# IMU.net
KiCad netlist of a schematic drawn in Altium Designer
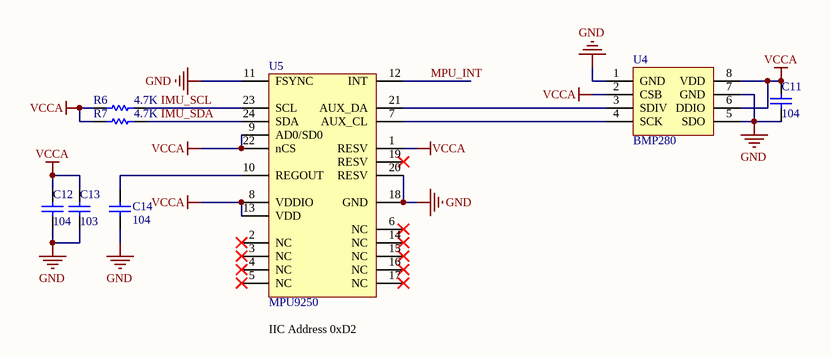
[diagram p0: IMU.SchDoc]

(export (version "E")
  (design (tool "Eeschema 10.0.6"))
  (components
    (comp (ref "C11")
      (value "104")
      (footprint "C0603")
      (description "电容")
      (fields (field (name "PUBLISHER") "Altium Limited"))
      (libsource (lib "Devices") (part "C0603"))
    )
    (comp (ref "C12")
      (value "104")
      (footprint "C0603")
      (description "电容")
      (fields (field (name "PUBLISHER") "Altium Limited"))
      (libsource (lib "Devices") (part "C0603"))
    )
    (comp (ref "C13")
      (value "103")
      (footprint "C0603")
      (description "电容")
      (fields (field (name "PUBLISHER") "Altium Limited"))
      (libsource (lib "Devices") (part "C0603"))
    )
    (comp (ref "C14")
      (value "104")
      (footprint "C0603")
      (description "电容")
      (fields (field (name "PUBLISHER") "Altium Limited"))
      (libsource (lib "Devices") (part "C0603"))
    )
    (comp (ref "R6")
      (value "4.7K")
      (footprint "R0603")
      (description "电阻")
      (fields (field (name "PUBLISHER") "Altium Limited"))
      (libsource (lib "Devices") (part "RES0603"))
    )
    (comp (ref "R7")
      (value "4.7K")
      (footprint "R0603")
      (description "电阻")
      (fields (field (name "PUBLISHER") "Altium Limited"))
      (libsource (lib "Devices") (part "RES0603"))
    )
    (comp (ref "U4")
      (value "BMP280")
      (footprint "LGA-8")
      (description "气压剂")
      (libsource (lib "IC") (part "BMP280"))
    )
    (comp (ref "U5")
      (value "MPU9250")
      (footprint "QFN-24-0.4")
      (description "9轴运动处理传感器")
      (libsource (lib "IC") (part "MPU9250"))
    )
  )
  (nets
    (net (code "1") (name "/IMU_SCL") (class "Default")
      (node (ref "R6") (pin "2") (pinfunction "2_2") (pintype "passive"))
      (node (ref "U5") (pin "23") (pinfunction "SCL_23") (pintype "passive"))
    )
    (net (code "2") (name "/IMU_SDA") (class "Default")
      (node (ref "R7") (pin "2") (pinfunction "2_2") (pintype "passive"))
      (node (ref "U5") (pin "24") (pinfunction "SDA_24") (pintype "passive"))
    )
    (net (code "3") (name "/MPU_INT") (class "Default")
      (node (ref "U5") (pin "12") (pinfunction "INT_12") (pintype "passive"))
    )
    (net (code "4") (name "GND") (class "Default")
      (node (ref "C11") (pin "1") (pinfunction "1_1") (pintype "passive"))
      (node (ref "C12") (pin "1") (pinfunction "1_1") (pintype "passive"))
      (node (ref "C13") (pin "1") (pinfunction "1_1") (pintype "passive"))
      (node (ref "C14") (pin "1") (pinfunction "1_1") (pintype "passive"))
      (node (ref "U4") (pin "1") (pinfunction "GND_1") (pintype "passive"))
      (node (ref "U4") (pin "5") (pinfunction "SDO_5") (pintype "passive"))
      (node (ref "U4") (pin "7") (pinfunction "GND_7") (pintype "passive"))
      (node (ref "U5") (pin "11") (pinfunction "FSYNC_11") (pintype "passive"))
      (node (ref "U5") (pin "18") (pinfunction "GND_18") (pintype "passive"))
      (node (ref "U5") (pin "20") (pinfunction "RESV_20") (pintype "passive"))
    )
    (net (code "5") (name "Net-(U4-SCK)") (class "Default")
      (node (ref "U4") (pin "4") (pinfunction "SCK_4") (pintype "passive"))
      (node (ref "U5") (pin "7") (pinfunction "AUX_CL_7") (pintype "passive"))
    )
    (net (code "6") (name "Net-(U4-SDIV)") (class "Default")
      (node (ref "U4") (pin "3") (pinfunction "SDIV_3") (pintype "passive"))
      (node (ref "U5") (pin "21") (pinfunction "AUX_DA_21") (pintype "passive"))
    )
    (net (code "7") (name "Net-(U5-REGOUT)") (class "Default")
      (node (ref "C14") (pin "2") (pinfunction "2_2") (pintype "passive"))
      (node (ref "U5") (pin "10") (pinfunction "REGOUT_10") (pintype "passive"))
    )
    (net (code "8") (name "VCCA") (class "Default")
      (node (ref "C11") (pin "2") (pinfunction "2_2") (pintype "passive"))
      (node (ref "C12") (pin "2") (pinfunction "2_2") (pintype "passive"))
      (node (ref "C13") (pin "2") (pinfunction "2_2") (pintype "passive"))
      (node (ref "R6") (pin "1") (pinfunction "1_1") (pintype "passive"))
      (node (ref "R7") (pin "1") (pinfunction "1_1") (pintype "passive"))
      (node (ref "U4") (pin "2") (pinfunction "CSB_2") (pintype "passive"))
      (node (ref "U4") (pin "6") (pinfunction "DDIO_6") (pintype "passive"))
      (node (ref "U4") (pin "8") (pinfunction "VDD_8") (pintype "passive"))
      (node (ref "U5") (pin "1") (pinfunction "RESV_1") (pintype "passive"))
      (node (ref "U5") (pin "13") (pinfunction "VDD_13") (pintype "passive"))
      (node (ref "U5") (pin "22") (pinfunction "nCS_22") (pintype "passive"))
      (node (ref "U5") (pin "8") (pinfunction "VDDIO_8") (pintype "passive"))
      (node (ref "U5") (pin "9") (pinfunction "AD0/SD0_9") (pintype "passive"))
    )
    (net (code "9") (name "unconnected-(U5-NC-Pad2)") (class "Default")
      (node (ref "U5") (pin "2") (pinfunction "NC_2") (pintype "passive+no_connect"))
    )
    (net (code "10") (name "unconnected-(U5-NC-Pad3)") (class "Default")
      (node (ref "U5") (pin "3") (pinfunction "NC_3") (pintype "passive+no_connect"))
    )
    (net (code "11") (name "unconnected-(U5-NC-Pad4)") (class "Default")
      (node (ref "U5") (pin "4") (pinfunction "NC_4") (pintype "passive+no_connect"))
    )
    (net (code "12") (name "unconnected-(U5-NC-Pad5)") (class "Default")
      (node (ref "U5") (pin "5") (pinfunction "NC_5") (pintype "passive+no_connect"))
    )
    (net (code "13") (name "unconnected-(U5-NC-Pad6)") (class "Default")
      (node (ref "U5") (pin "6") (pinfunction "NC_6") (pintype "passive+no_connect"))
    )
    (net (code "14") (name "unconnected-(U5-NC-Pad14)") (class "Default")
      (node (ref "U5") (pin "14") (pinfunction "NC_14") (pintype "passive+no_connect"))
    )
    (net (code "15") (name "unconnected-(U5-NC-Pad15)") (class "Default")
      (node (ref "U5") (pin "15") (pinfunction "NC_15") (pintype "passive+no_connect"))
    )
    (net (code "16") (name "unconnected-(U5-NC-Pad16)") (class "Default")
      (node (ref "U5") (pin "16") (pinfunction "NC_16") (pintype "passive+no_connect"))
    )
    (net (code "17") (name "unconnected-(U5-NC-Pad17)") (class "Default")
      (node (ref "U5") (pin "17") (pinfunction "NC_17") (pintype "passive+no_connect"))
    )
    (net (code "18") (name "unconnected-(U5-RESV-Pad19)") (class "Default")
      (node (ref "U5") (pin "19") (pinfunction "RESV_19") (pintype "passive+no_connect"))
    )
  )
)
